# ControleLeds.net
KiCad netlist of a schematic drawn in Altium Designer
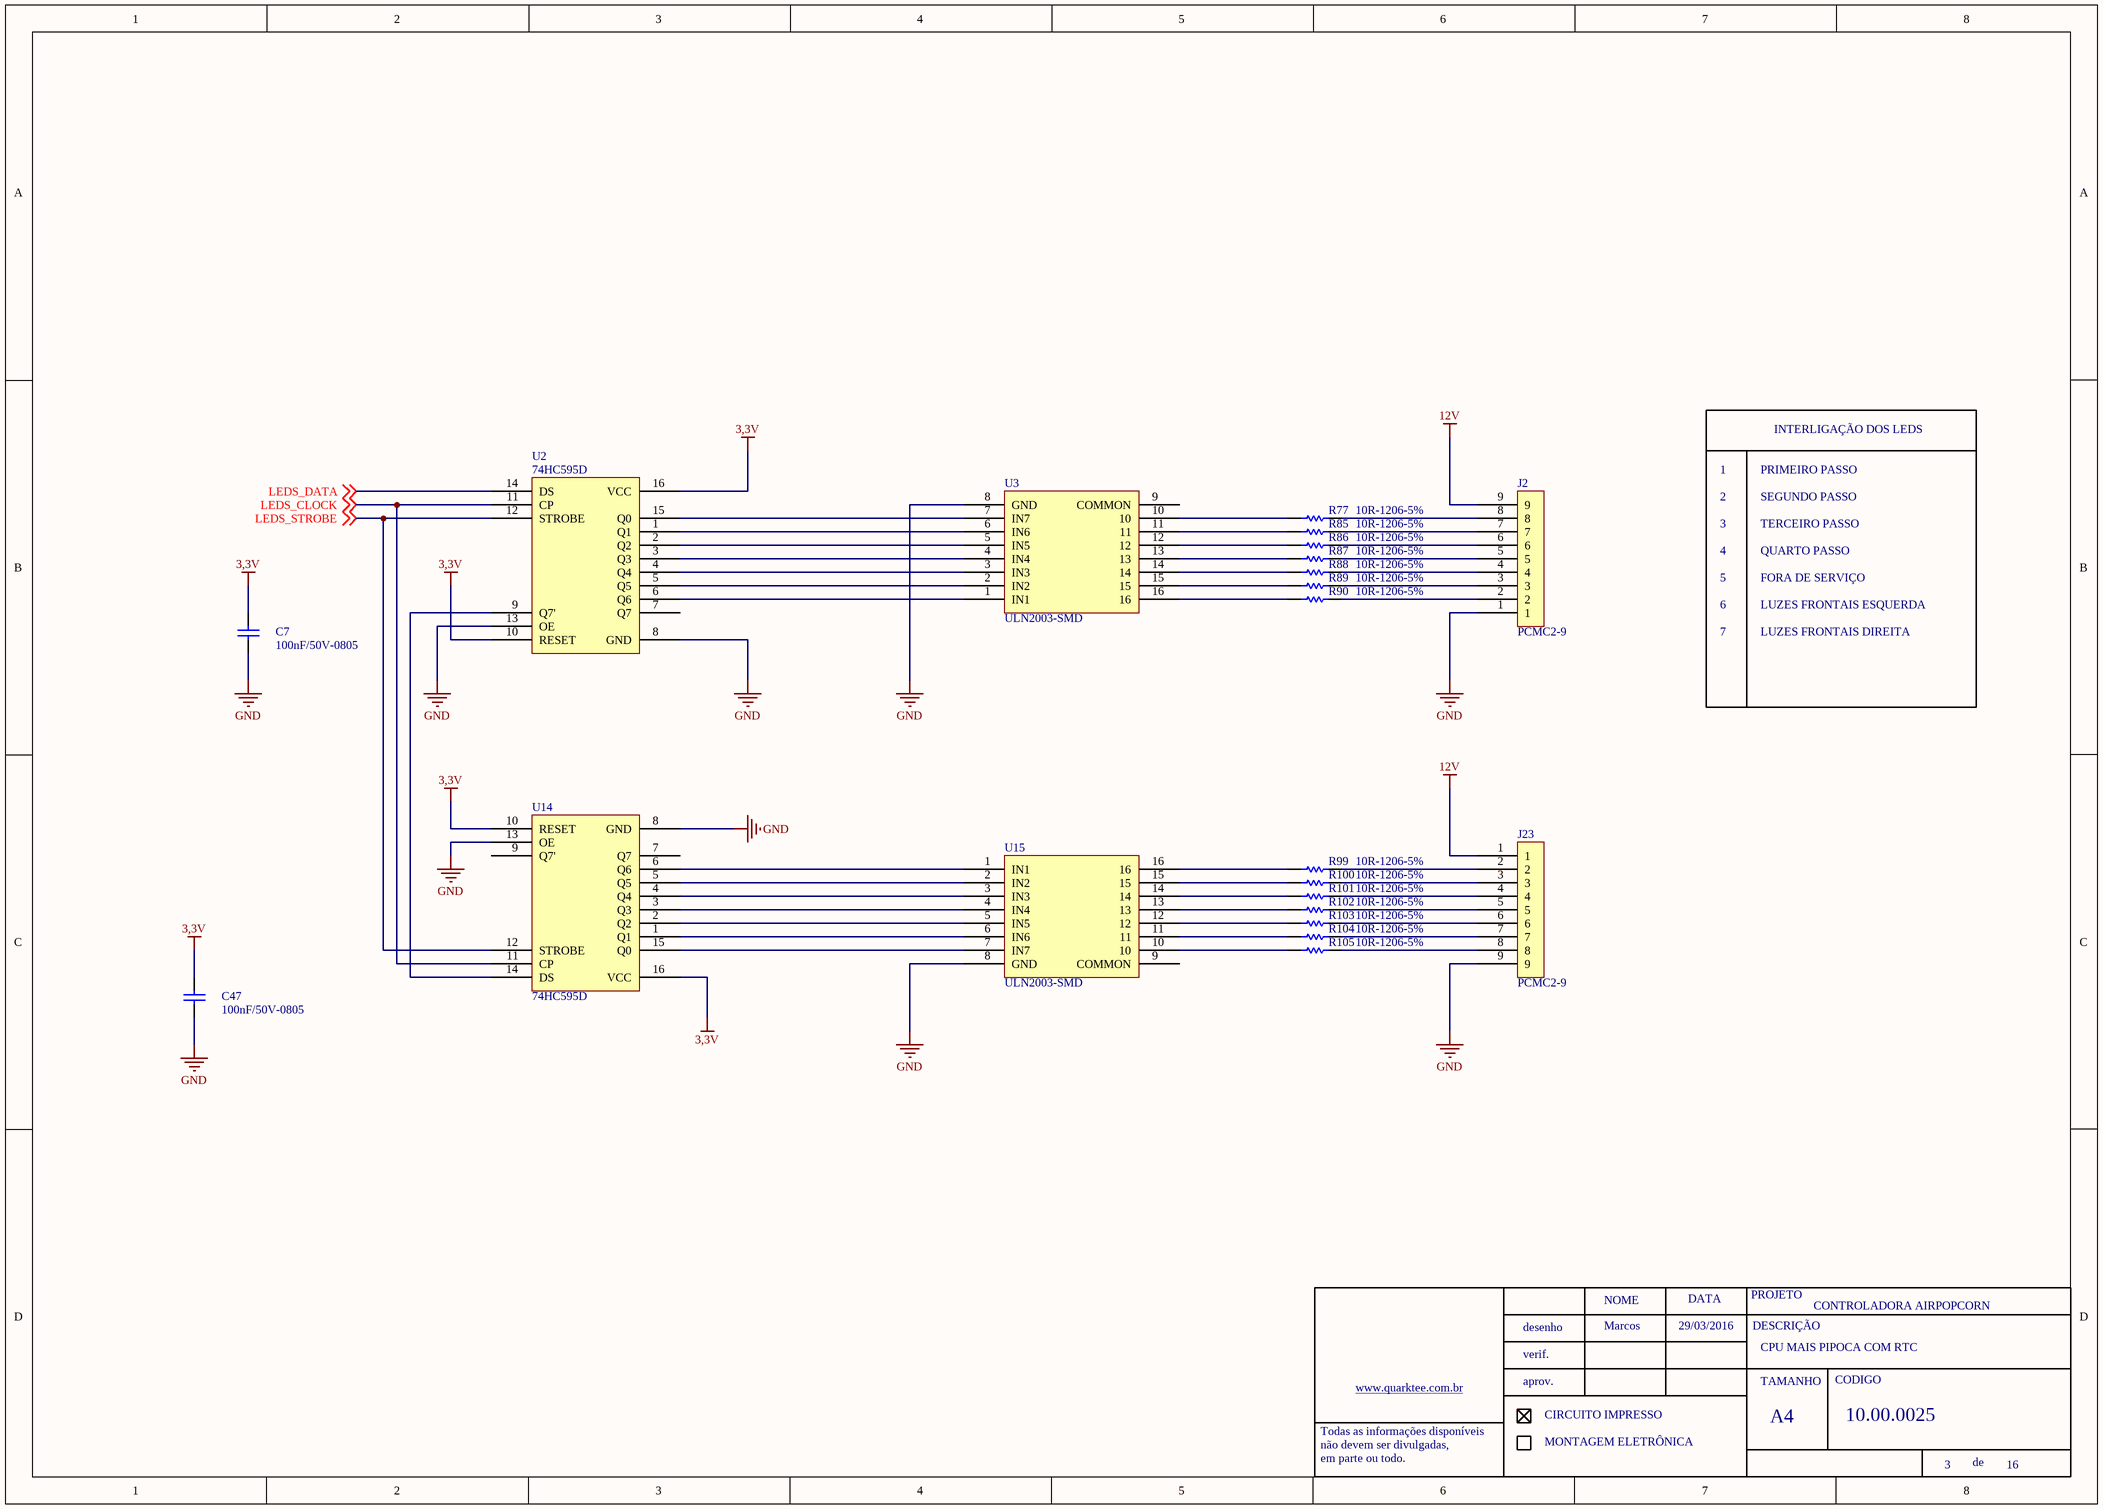
[diagram p0: ControleLeds.SchDoc]

(export (version "E")
  (design (tool "Eeschema 10.0.6"))
  (components
    (comp (ref "C7")
      (value "100nF/50V-0805")
      (footprint "0805-REVISADO O")
      (description "100nF/50-0805-NPO")
      (libsource (lib "AquinoLib") (part "100nF/50-0805-NPO"))
    )
    (comp (ref "C47")
      (value "100nF/50V-0805")
      (footprint "0805-REVISADO O")
      (description "100nF/50-0805-NPO")
      (libsource (lib "AquinoLib") (part "100nF/50-0805-NPO"))
    )
    (comp (ref "J2") (value "PCMC2-9") (footprint "PCMC2-9") (libsource (lib "") (part "PCMC2-9_1")))
    (comp (ref "J23") (value "PCMC2-9") (footprint "PCMC2-9") (libsource (lib "AquinoLib") (part "PCMC2-9")))
    (comp (ref "R77")
      (value "10R-1206-5%")
      (footprint "1206-REVISADO O")
      (description "10R-0805-5%")
      (libsource (lib "AquinoLib") (part "10R-0805-5%"))
    )
    (comp (ref "R85")
      (value "10R-1206-5%")
      (footprint "1206-REVISADO O")
      (description "10R-0805-5%")
      (libsource (lib "AquinoLib") (part "10R-0805-5%"))
    )
    (comp (ref "R86")
      (value "10R-1206-5%")
      (footprint "1206-REVISADO O")
      (description "10R-0805-5%")
      (libsource (lib "AquinoLib") (part "10R-0805-5%"))
    )
    (comp (ref "R87")
      (value "10R-1206-5%")
      (footprint "1206-REVISADO O")
      (description "10R-0805-5%")
      (libsource (lib "AquinoLib") (part "10R-0805-5%"))
    )
    (comp (ref "R88")
      (value "10R-1206-5%")
      (footprint "1206-REVISADO O")
      (description "10R-0805-5%")
      (libsource (lib "AquinoLib") (part "10R-0805-5%"))
    )
    (comp (ref "R89")
      (value "10R-1206-5%")
      (footprint "1206-REVISADO O")
      (description "10R-0805-5%")
      (libsource (lib "AquinoLib") (part "10R-0805-5%"))
    )
    (comp (ref "R90")
      (value "10R-1206-5%")
      (footprint "1206-REVISADO O")
      (description "10R-0805-5%")
      (libsource (lib "AquinoLib") (part "10R-0805-5%"))
    )
    (comp (ref "R99")
      (value "10R-1206-5%")
      (footprint "1206-REVISADO O")
      (description "10R-0805-5%")
      (libsource (lib "AquinoLib") (part "10R-0805-5%"))
    )
    (comp (ref "R100")
      (value "10R-1206-5%")
      (footprint "1206-REVISADO O")
      (description "10R-0805-5%")
      (libsource (lib "AquinoLib") (part "10R-0805-5%"))
    )
    (comp (ref "R101")
      (value "10R-1206-5%")
      (footprint "1206-REVISADO O")
      (description "10R-0805-5%")
      (libsource (lib "AquinoLib") (part "10R-0805-5%"))
    )
    (comp (ref "R102")
      (value "10R-1206-5%")
      (footprint "1206-REVISADO O")
      (description "10R-0805-5%")
      (libsource (lib "AquinoLib") (part "10R-0805-5%"))
    )
    (comp (ref "R103")
      (value "10R-1206-5%")
      (footprint "1206-REVISADO O")
      (description "10R-0805-5%")
      (libsource (lib "AquinoLib") (part "10R-0805-5%"))
    )
    (comp (ref "R104")
      (value "10R-1206-5%")
      (footprint "1206-REVISADO O")
      (description "10R-0805-5%")
      (libsource (lib "AquinoLib") (part "10R-0805-5%"))
    )
    (comp (ref "R105")
      (value "10R-1206-5%")
      (footprint "1206-REVISADO O")
      (description "10R-0805-5%")
      (libsource (lib "AquinoLib") (part "10R-0805-5%"))
    )
    (comp (ref "U2") (value "74HC595D") (footprint "SOIC 16 PINOS") (libsource (lib "") (part "74HC595D_1")))
    (comp (ref "U3")
      (value "ULN2003-SMD")
      (footprint "SOIC 16 PINOS")
      (description "ULN2003")
      (libsource (lib "AquinoLib") (part "ULN2003"))
    )
    (comp (ref "U14")
      (value "74HC595D")
      (footprint "SOIC 16 PINOS")
      (libsource (lib "ChaveDigital3") (part "74HC595D"))
    )
    (comp (ref "U15")
      (value "ULN2003-SMD")
      (footprint "SOIC 16 PINOS")
      (description "ULN2003")
      (libsource (lib "") (part "ULN2003_1"))
    )
  )
  (nets
    (net (code "1") (name "3,3V") (class "Default")
      (node (ref "C47") (pin "2") (pinfunction "2_2") (pintype "passive"))
      (node (ref "C7") (pin "2") (pinfunction "2_2") (pintype "passive"))
      (node (ref "U14") (pin "10") (pinfunction "RESET_10") (pintype "passive"))
      (node (ref "U14") (pin "16") (pinfunction "VCC_16") (pintype "passive"))
      (node (ref "U2") (pin "10") (pinfunction "RESET_10") (pintype "passive"))
      (node (ref "U2") (pin "16") (pinfunction "VCC_16") (pintype "passive"))
    )
    (net (code "2") (name "12V") (class "Default")
      (node (ref "J2") (pin "9") (pinfunction "9_9") (pintype "passive"))
      (node (ref "J23") (pin "1") (pinfunction "1_1") (pintype "passive"))
    )
    (net (code "3") (name "GND") (class "Default")
      (node (ref "C47") (pin "1") (pinfunction "1_1") (pintype "passive"))
      (node (ref "C7") (pin "1") (pinfunction "1_1") (pintype "passive"))
      (node (ref "J2") (pin "1") (pinfunction "1_1") (pintype "passive"))
      (node (ref "J23") (pin "9") (pinfunction "9_9") (pintype "passive"))
      (node (ref "U14") (pin "13") (pinfunction "OE_13") (pintype "passive"))
      (node (ref "U14") (pin "8") (pinfunction "GND_8") (pintype "passive"))
      (node (ref "U15") (pin "8") (pinfunction "GND_8") (pintype "passive"))
      (node (ref "U2") (pin "13") (pinfunction "OE_13") (pintype "passive"))
      (node (ref "U2") (pin "8") (pinfunction "GND_8") (pintype "passive"))
      (node (ref "U3") (pin "8") (pinfunction "GND_8") (pintype "passive"))
    )
    (net (code "4") (name "LEDS_CLOCK") (class "Default")
      (node (ref "U14") (pin "11") (pinfunction "CP_11") (pintype "passive"))
      (node (ref "U2") (pin "11") (pinfunction "CP_11") (pintype "passive"))
    )
    (net (code "5") (name "LEDS_DATA") (class "Default")
      (node (ref "U2") (pin "14") (pinfunction "DS_14") (pintype "passive"))
    )
    (net (code "6") (name "LEDS_STROBE") (class "Default")
      (node (ref "U14") (pin "12") (pinfunction "STROBE_12") (pintype "passive"))
      (node (ref "U2") (pin "12") (pinfunction "STROBE_12") (pintype "passive"))
    )
    (net (code "7") (name "Net-(J2-Pad2)") (class "Default")
      (node (ref "J2") (pin "2") (pinfunction "2_2") (pintype "passive"))
      (node (ref "R90") (pin "2") (pinfunction "2_2") (pintype "passive"))
    )
    (net (code "8") (name "Net-(J2-Pad3)") (class "Default")
      (node (ref "J2") (pin "3") (pinfunction "3_3") (pintype "passive"))
      (node (ref "R89") (pin "2") (pinfunction "2_2") (pintype "passive"))
    )
    (net (code "9") (name "Net-(J2-Pad4)") (class "Default")
      (node (ref "J2") (pin "4") (pinfunction "4_4") (pintype "passive"))
      (node (ref "R88") (pin "2") (pinfunction "2_2") (pintype "passive"))
    )
    (net (code "10") (name "Net-(J2-Pad5)") (class "Default")
      (node (ref "J2") (pin "5") (pinfunction "5_5") (pintype "passive"))
      (node (ref "R87") (pin "2") (pinfunction "2_2") (pintype "passive"))
    )
    (net (code "11") (name "Net-(J2-Pad6)") (class "Default")
      (node (ref "J2") (pin "6") (pinfunction "6_6") (pintype "passive"))
      (node (ref "R86") (pin "2") (pinfunction "2_2") (pintype "passive"))
    )
    (net (code "12") (name "Net-(J2-Pad7)") (class "Default")
      (node (ref "J2") (pin "7") (pinfunction "7_7") (pintype "passive"))
      (node (ref "R85") (pin "2") (pinfunction "2_2") (pintype "passive"))
    )
    (net (code "13") (name "Net-(J2-Pad8)") (class "Default")
      (node (ref "J2") (pin "8") (pinfunction "8_8") (pintype "passive"))
      (node (ref "R77") (pin "2") (pinfunction "2_2") (pintype "passive"))
    )
    (net (code "14") (name "Net-(J23-Pad2)") (class "Default")
      (node (ref "J23") (pin "2") (pinfunction "2_2") (pintype "passive"))
      (node (ref "R99") (pin "2") (pinfunction "2_2") (pintype "passive"))
    )
    (net (code "15") (name "Net-(J23-Pad3)") (class "Default")
      (node (ref "J23") (pin "3") (pinfunction "3_3") (pintype "passive"))
      (node (ref "R100") (pin "2") (pinfunction "2_2") (pintype "passive"))
    )
    (net (code "16") (name "Net-(J23-Pad4)") (class "Default")
      (node (ref "J23") (pin "4") (pinfunction "4_4") (pintype "passive"))
      (node (ref "R101") (pin "2") (pinfunction "2_2") (pintype "passive"))
    )
    (net (code "17") (name "Net-(J23-Pad5)") (class "Default")
      (node (ref "J23") (pin "5") (pinfunction "5_5") (pintype "passive"))
      (node (ref "R102") (pin "2") (pinfunction "2_2") (pintype "passive"))
    )
    (net (code "18") (name "Net-(J23-Pad6)") (class "Default")
      (node (ref "J23") (pin "6") (pinfunction "6_6") (pintype "passive"))
      (node (ref "R103") (pin "2") (pinfunction "2_2") (pintype "passive"))
    )
    (net (code "19") (name "Net-(J23-Pad7)") (class "Default")
      (node (ref "J23") (pin "7") (pinfunction "7_7") (pintype "passive"))
      (node (ref "R104") (pin "2") (pinfunction "2_2") (pintype "passive"))
    )
    (net (code "20") (name "Net-(J23-Pad8)") (class "Default")
      (node (ref "J23") (pin "8") (pinfunction "8_8") (pintype "passive"))
      (node (ref "R105") (pin "2") (pinfunction "2_2") (pintype "passive"))
    )
    (net (code "21") (name "Net-(R77-Pad1)") (class "Default")
      (node (ref "R77") (pin "1") (pinfunction "1_1") (pintype "passive"))
      (node (ref "U3") (pin "10") (pinfunction "10_10") (pintype "passive"))
    )
    (net (code "22") (name "Net-(R85-Pad1)") (class "Default")
      (node (ref "R85") (pin "1") (pinfunction "1_1") (pintype "passive"))
      (node (ref "U3") (pin "11") (pinfunction "11_11") (pintype "passive"))
    )
    (net (code "23") (name "Net-(R86-Pad1)") (class "Default")
      (node (ref "R86") (pin "1") (pinfunction "1_1") (pintype "passive"))
      (node (ref "U3") (pin "12") (pinfunction "12_12") (pintype "passive"))
    )
    (net (code "24") (name "Net-(R87-Pad1)") (class "Default")
      (node (ref "R87") (pin "1") (pinfunction "1_1") (pintype "passive"))
      (node (ref "U3") (pin "13") (pinfunction "13_13") (pintype "passive"))
    )
    (net (code "25") (name "Net-(R88-Pad1)") (class "Default")
      (node (ref "R88") (pin "1") (pinfunction "1_1") (pintype "passive"))
      (node (ref "U3") (pin "14") (pinfunction "14_14") (pintype "passive"))
    )
    (net (code "26") (name "Net-(R89-Pad1)") (class "Default")
      (node (ref "R89") (pin "1") (pinfunction "1_1") (pintype "passive"))
      (node (ref "U3") (pin "15") (pinfunction "15_15") (pintype "passive"))
    )
    (net (code "27") (name "Net-(R90-Pad1)") (class "Default")
      (node (ref "R90") (pin "1") (pinfunction "1_1") (pintype "passive"))
      (node (ref "U3") (pin "16") (pinfunction "16_16") (pintype "passive"))
    )
    (net (code "28") (name "Net-(R99-Pad1)") (class "Default")
      (node (ref "R99") (pin "1") (pinfunction "1_1") (pintype "passive"))
      (node (ref "U15") (pin "16") (pinfunction "16_16") (pintype "passive"))
    )
    (net (code "29") (name "Net-(R100-Pad1)") (class "Default")
      (node (ref "R100") (pin "1") (pinfunction "1_1") (pintype "passive"))
      (node (ref "U15") (pin "15") (pinfunction "15_15") (pintype "passive"))
    )
    (net (code "30") (name "Net-(R101-Pad1)") (class "Default")
      (node (ref "R101") (pin "1") (pinfunction "1_1") (pintype "passive"))
      (node (ref "U15") (pin "14") (pinfunction "14_14") (pintype "passive"))
    )
    (net (code "31") (name "Net-(R102-Pad1)") (class "Default")
      (node (ref "R102") (pin "1") (pinfunction "1_1") (pintype "passive"))
      (node (ref "U15") (pin "13") (pinfunction "13_13") (pintype "passive"))
    )
    (net (code "32") (name "Net-(R103-Pad1)") (class "Default")
      (node (ref "R103") (pin "1") (pinfunction "1_1") (pintype "passive"))
      (node (ref "U15") (pin "12") (pinfunction "12_12") (pintype "passive"))
    )
    (net (code "33") (name "Net-(R104-Pad1)") (class "Default")
      (node (ref "R104") (pin "1") (pinfunction "1_1") (pintype "passive"))
      (node (ref "U15") (pin "11") (pinfunction "11_11") (pintype "passive"))
    )
    (net (code "34") (name "Net-(R105-Pad1)") (class "Default")
      (node (ref "R105") (pin "1") (pinfunction "1_1") (pintype "passive"))
      (node (ref "U15") (pin "10") (pinfunction "10_10") (pintype "passive"))
    )
    (net (code "35") (name "Net-(U2-Q0)") (class "Default")
      (node (ref "U2") (pin "15") (pinfunction "Q0_15") (pintype "passive"))
      (node (ref "U3") (pin "7") (pinfunction "IN7_7") (pintype "passive"))
    )
    (net (code "36") (name "Net-(U2-Q1)") (class "Default")
      (node (ref "U2") (pin "1") (pinfunction "Q1_1") (pintype "passive"))
      (node (ref "U3") (pin "6") (pinfunction "IN6_6") (pintype "passive"))
    )
    (net (code "37") (name "Net-(U2-Q2)") (class "Default")
      (node (ref "U2") (pin "2") (pinfunction "Q2_2") (pintype "passive"))
      (node (ref "U3") (pin "5") (pinfunction "IN5_5") (pintype "passive"))
    )
    (net (code "38") (name "Net-(U2-Q3)") (class "Default")
      (node (ref "U2") (pin "3") (pinfunction "Q3_3") (pintype "passive"))
      (node (ref "U3") (pin "4") (pinfunction "IN4_4") (pintype "passive"))
    )
    (net (code "39") (name "Net-(U2-Q4)") (class "Default")
      (node (ref "U2") (pin "4") (pinfunction "Q4_4") (pintype "passive"))
      (node (ref "U3") (pin "3") (pinfunction "IN3_3") (pintype "passive"))
    )
    (net (code "40") (name "Net-(U2-Q5)") (class "Default")
      (node (ref "U2") (pin "5") (pinfunction "Q5_5") (pintype "passive"))
      (node (ref "U3") (pin "2") (pinfunction "IN2_2") (pintype "passive"))
    )
    (net (code "41") (name "Net-(U2-Q6)") (class "Default")
      (node (ref "U2") (pin "6") (pinfunction "Q6_6") (pintype "passive"))
      (node (ref "U3") (pin "1") (pinfunction "IN1_1") (pintype "passive"))
    )
    (net (code "42") (name "Net-(U14-DS)") (class "Default")
      (node (ref "U14") (pin "14") (pinfunction "DS_14") (pintype "passive"))
      (node (ref "U2") (pin "9") (pinfunction "Q7'_9") (pintype "passive"))
    )
    (net (code "43") (name "Net-(U14-Q0)") (class "Default")
      (node (ref "U14") (pin "15") (pinfunction "Q0_15") (pintype "passive"))
      (node (ref "U15") (pin "7") (pinfunction "IN7_7") (pintype "passive"))
    )
    (net (code "44") (name "Net-(U14-Q1)") (class "Default")
      (node (ref "U14") (pin "1") (pinfunction "Q1_1") (pintype "passive"))
      (node (ref "U15") (pin "6") (pinfunction "IN6_6") (pintype "passive"))
    )
    (net (code "45") (name "Net-(U14-Q2)") (class "Default")
      (node (ref "U14") (pin "2") (pinfunction "Q2_2") (pintype "passive"))
      (node (ref "U15") (pin "5") (pinfunction "IN5_5") (pintype "passive"))
    )
    (net (code "46") (name "Net-(U14-Q3)") (class "Default")
      (node (ref "U14") (pin "3") (pinfunction "Q3_3") (pintype "passive"))
      (node (ref "U15") (pin "4") (pinfunction "IN4_4") (pintype "passive"))
    )
    (net (code "47") (name "Net-(U14-Q4)") (class "Default")
      (node (ref "U14") (pin "4") (pinfunction "Q4_4") (pintype "passive"))
      (node (ref "U15") (pin "3") (pinfunction "IN3_3") (pintype "passive"))
    )
    (net (code "48") (name "Net-(U14-Q5)") (class "Default")
      (node (ref "U14") (pin "5") (pinfunction "Q5_5") (pintype "passive"))
      (node (ref "U15") (pin "2") (pinfunction "IN2_2") (pintype "passive"))
    )
    (net (code "49") (name "Net-(U14-Q6)") (class "Default")
      (node (ref "U14") (pin "6") (pinfunction "Q6_6") (pintype "passive"))
      (node (ref "U15") (pin "1") (pinfunction "IN1_1") (pintype "passive"))
    )
    (net (code "50") (name "unconnected-(U2-Q7-Pad7)") (class "Default")
      (node (ref "U2") (pin "7") (pinfunction "Q7_7") (pintype "passive"))
    )
    (net (code "51") (name "unconnected-(U3-COMMON-Pad9)") (class "Default")
      (node (ref "U3") (pin "9") (pinfunction "COMMON_9") (pintype "passive"))
    )
    (net (code "52") (name "unconnected-(U14-Q7'-Pad9)") (class "Default")
      (node (ref "U14") (pin "9") (pinfunction "Q7'_9") (pintype "passive"))
    )
    (net (code "53") (name "unconnected-(U14-Q7-Pad7)") (class "Default")
      (node (ref "U14") (pin "7") (pinfunction "Q7_7") (pintype "passive"))
    )
    (net (code "54") (name "unconnected-(U15-COMMON-Pad9)") (class "Default")
      (node (ref "U15") (pin "9") (pinfunction "COMMON_9") (pintype "passive"))
    )
  )
)
